# macropad_v1.net
KiCad netlist of a schematic drawn in EAGLE
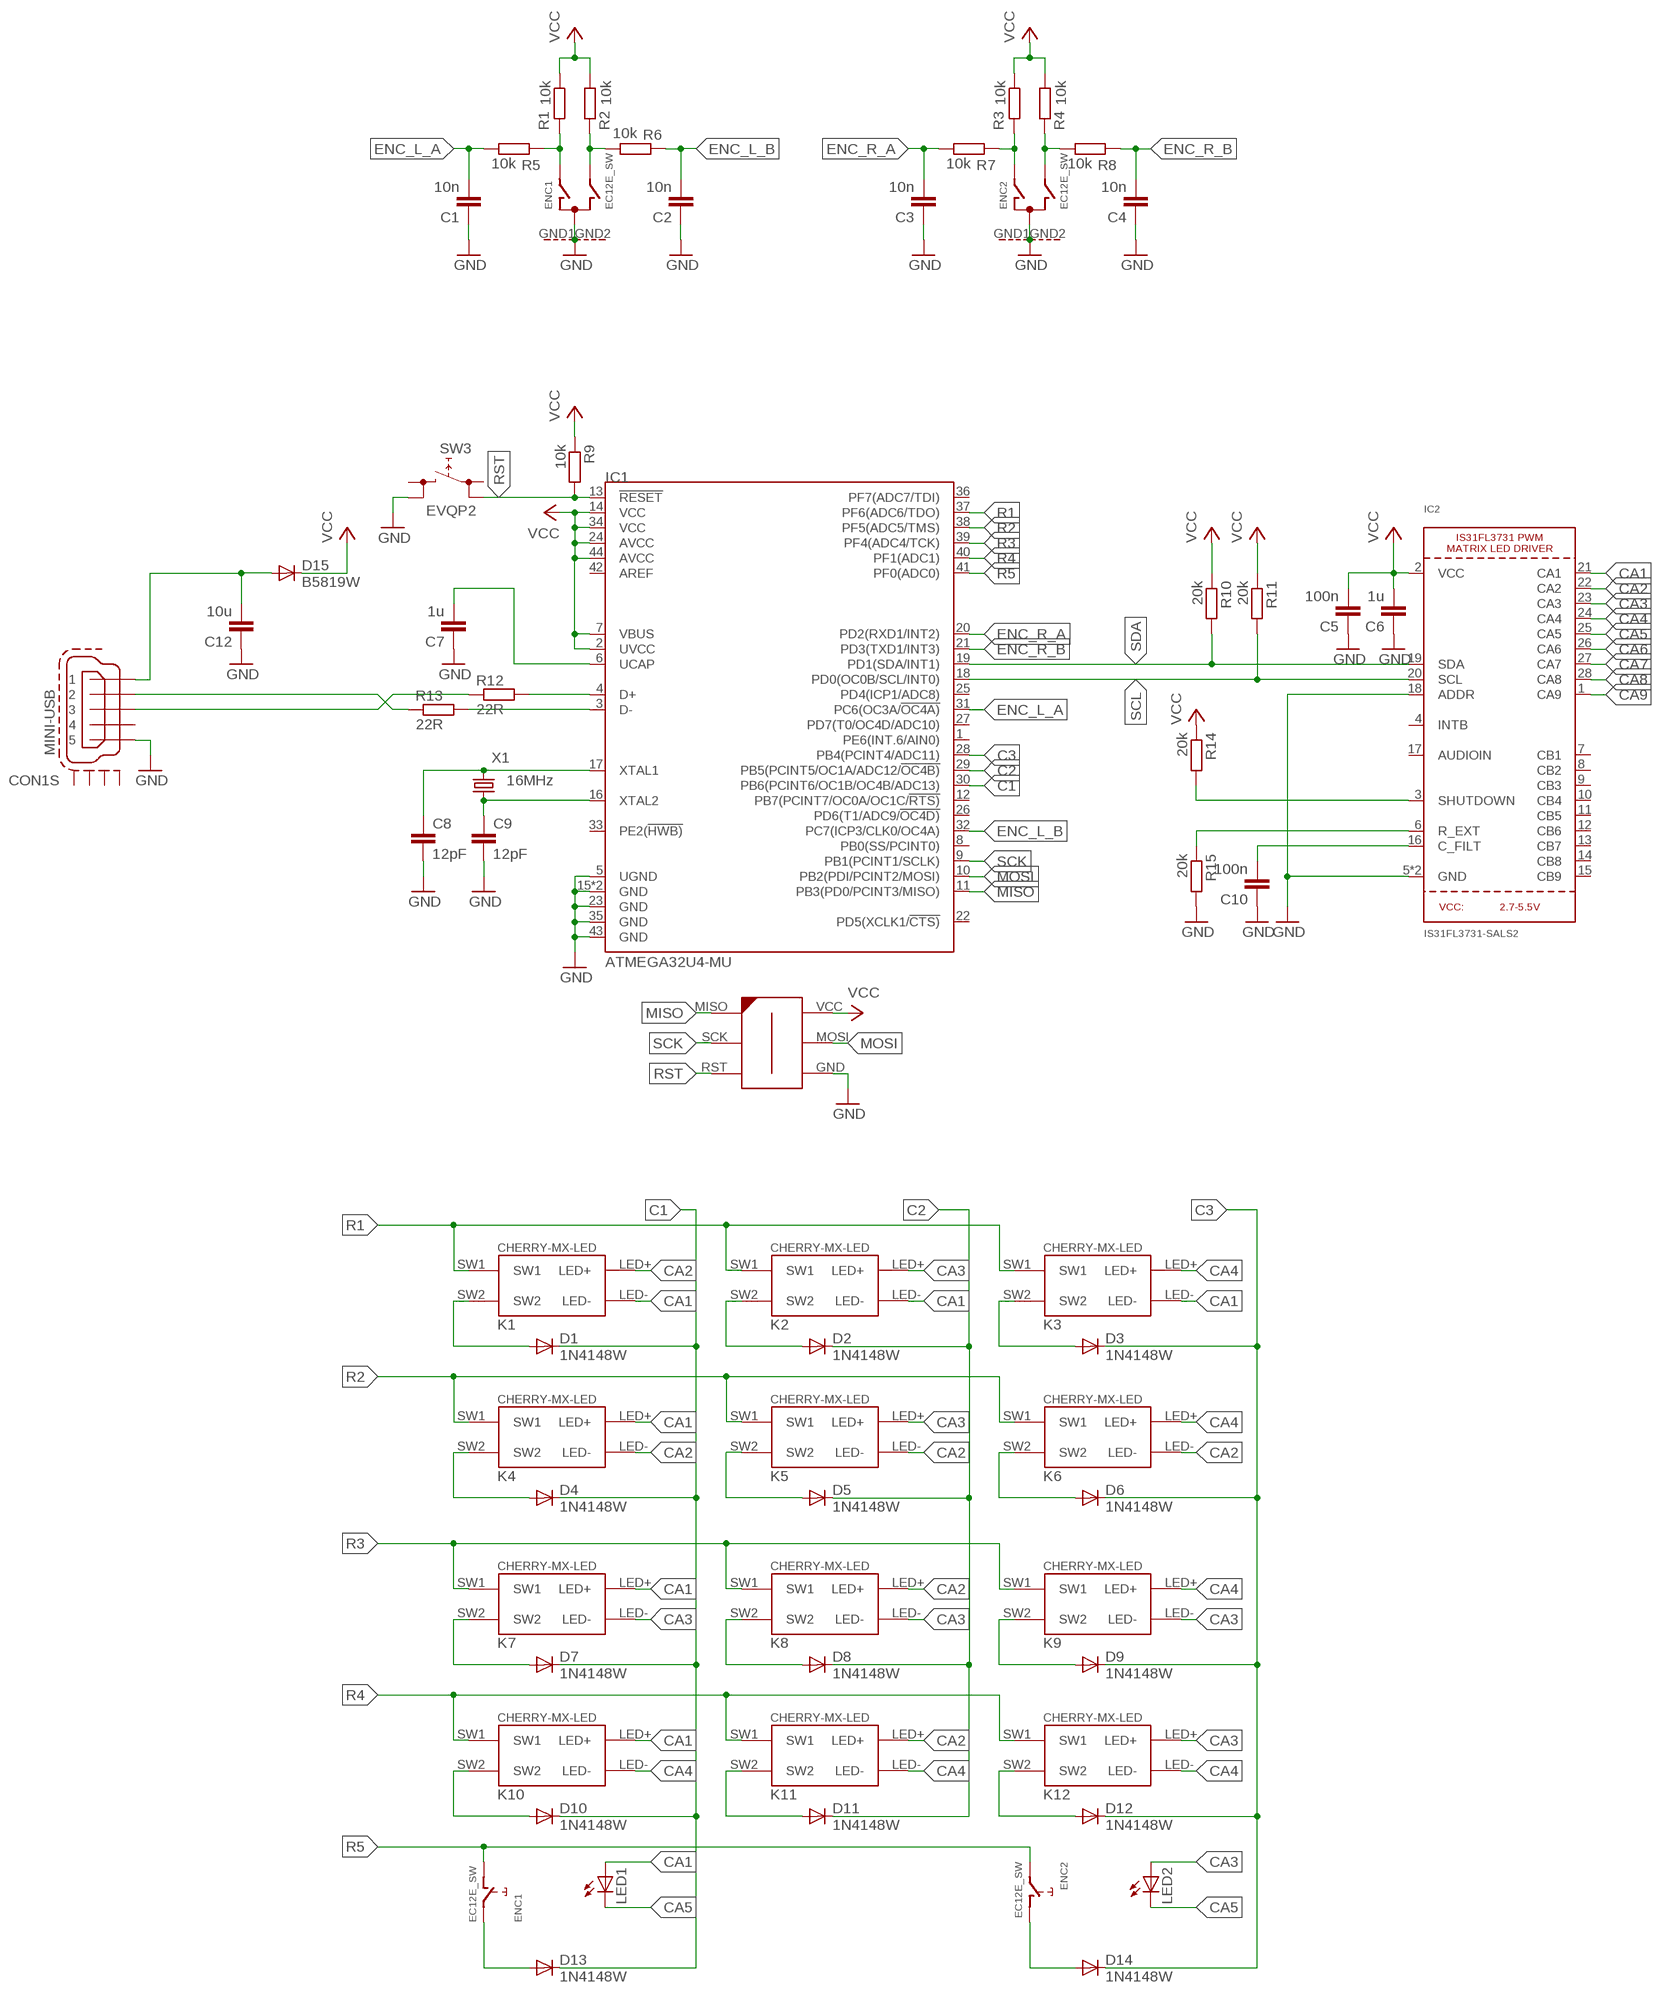
[diagram p0: schematic, sheet 1]

(export (version "E")
  (design (tool "Eeschema 10.0.6"))
  (components
    (comp (ref "C1")
      (value "10n")
      (footprint "eagle-import:C0603")
      (libsource (lib "eagle-import") (part "C-EUC0603"))
    )
    (comp (ref "C2")
      (value "10n")
      (footprint "eagle-import:C0603")
      (libsource (lib "eagle-import") (part "C-EUC0603"))
    )
    (comp (ref "C3")
      (value "10n")
      (footprint "eagle-import:C0603")
      (libsource (lib "eagle-import") (part "C-EUC0603"))
    )
    (comp (ref "C4")
      (value "10n")
      (footprint "eagle-import:C0603")
      (libsource (lib "eagle-import") (part "C-EUC0603"))
    )
    (comp (ref "C5")
      (value "100n")
      (footprint "eagle-import:C0603")
      (libsource (lib "eagle-import") (part "C-EUC0603"))
    )
    (comp (ref "C6")
      (value "1u")
      (footprint "eagle-import:C0603")
      (libsource (lib "eagle-import") (part "C-EUC0603"))
    )
    (comp (ref "C7")
      (value "1u")
      (footprint "eagle-import:C0603")
      (libsource (lib "eagle-import") (part "C-EUC0603"))
    )
    (comp (ref "C8")
      (value "12pF")
      (footprint "eagle-import:C0603")
      (libsource (lib "eagle-import") (part "C-EUC0603"))
    )
    (comp (ref "C9")
      (value "12pF")
      (footprint "eagle-import:C0603")
      (libsource (lib "eagle-import") (part "C-EUC0603"))
    )
    (comp (ref "C10")
      (value "100n")
      (footprint "eagle-import:C0603")
      (libsource (lib "eagle-import") (part "C-EUC0603"))
    )
    (comp (ref "C12")
      (value "10u")
      (footprint "eagle-import:C0603")
      (libsource (lib "eagle-import") (part "C-EUC0603"))
    )
    (comp (ref "CON1")
      (value "MINI-USB")
      (footprint "eagle-import:32005-201")
      (libsource (lib "eagle-import") (part "MINI-USB-SCHIELD-32005-201"))
    )
    (comp (ref "D1")
      (value "1N4148W")
      (footprint "eagle-import:SOD123")
      (libsource (lib "eagle-import") (part "DIODE-SOD123"))
    )
    (comp (ref "D2")
      (value "1N4148W")
      (footprint "eagle-import:SOD123")
      (libsource (lib "eagle-import") (part "DIODE-SOD123"))
    )
    (comp (ref "D3")
      (value "1N4148W")
      (footprint "eagle-import:SOD123")
      (libsource (lib "eagle-import") (part "DIODE-SOD123"))
    )
    (comp (ref "D4")
      (value "1N4148W")
      (footprint "eagle-import:SOD123")
      (libsource (lib "eagle-import") (part "DIODE-SOD123"))
    )
    (comp (ref "D5")
      (value "1N4148W")
      (footprint "eagle-import:SOD123")
      (libsource (lib "eagle-import") (part "DIODE-SOD123"))
    )
    (comp (ref "D6")
      (value "1N4148W")
      (footprint "eagle-import:SOD123")
      (libsource (lib "eagle-import") (part "DIODE-SOD123"))
    )
    (comp (ref "D7")
      (value "1N4148W")
      (footprint "eagle-import:SOD123")
      (libsource (lib "eagle-import") (part "DIODE-SOD123"))
    )
    (comp (ref "D8")
      (value "1N4148W")
      (footprint "eagle-import:SOD123")
      (libsource (lib "eagle-import") (part "DIODE-SOD123"))
    )
    (comp (ref "D9")
      (value "1N4148W")
      (footprint "eagle-import:SOD123")
      (libsource (lib "eagle-import") (part "DIODE-SOD123"))
    )
    (comp (ref "D10")
      (value "1N4148W")
      (footprint "eagle-import:SOD123")
      (libsource (lib "eagle-import") (part "DIODE-SOD123"))
    )
    (comp (ref "D11")
      (value "1N4148W")
      (footprint "eagle-import:SOD123")
      (libsource (lib "eagle-import") (part "DIODE-SOD123"))
    )
    (comp (ref "D12")
      (value "1N4148W")
      (footprint "eagle-import:SOD123")
      (libsource (lib "eagle-import") (part "DIODE-SOD123"))
    )
    (comp (ref "D13")
      (value "1N4148W")
      (footprint "eagle-import:SOD123")
      (libsource (lib "eagle-import") (part "DIODE-SOD123"))
    )
    (comp (ref "D14")
      (value "1N4148W")
      (footprint "eagle-import:SOD123")
      (libsource (lib "eagle-import") (part "DIODE-SOD123"))
    )
    (comp (ref "D15")
      (value "B5819W")
      (footprint "eagle-import:SOD123")
      (libsource (lib "eagle-import") (part "DIODE-SOD123"))
    )
    (comp (ref "ENC1")
      (value "EC12E_SW")
      (footprint "eagle-import:ALPS_EC12E_SW")
      (fields (field (name "MPN") "EC12E2424407"))
      (libsource (lib "eagle-import") (part "EC12E_SW"))
    )
    (comp (ref "ENC2")
      (value "EC12E_SW")
      (footprint "eagle-import:ALPS_EC12E_SW")
      (fields (field (name "MPN") "EC12E2424407"))
      (libsource (lib "eagle-import") (part "EC12E_SW"))
    )
    (comp (ref "IC1")
      (value "ATMEGA32U4-MU")
      (footprint "eagle-import:QFN44G-0.5-7X7MM")
      (fields (field (name "MF") "Microchip") (field (name "MP") "ATMEGA32U4-MUR"))
      (libsource (lib "eagle-import") (part "MCU-ATMEGA32U4-MUR(VQFN44)"))
    )
    (comp (ref "IC2")
      (value "IS31FL3731-SALS2")
      (footprint "eagle-import:QFN28_4MM_0.4MM")
      (libsource (lib "eagle-import") (part "IS31FL3731QFN"))
    )
    (comp (ref "K1")
      (value "CHERRY-MX-LED")
      (footprint "eagle-import:CHERRY-MX-LED")
      (libsource (lib "eagle-import") (part "CHERRY-MX-LED"))
    )
    (comp (ref "K2")
      (value "CHERRY-MX-LED")
      (footprint "eagle-import:CHERRY-MX-LED")
      (libsource (lib "eagle-import") (part "CHERRY-MX-LED"))
    )
    (comp (ref "K3")
      (value "CHERRY-MX-LED")
      (footprint "eagle-import:CHERRY-MX-LED")
      (libsource (lib "eagle-import") (part "CHERRY-MX-LED"))
    )
    (comp (ref "K4")
      (value "CHERRY-MX-LED")
      (footprint "eagle-import:CHERRY-MX-LED")
      (libsource (lib "eagle-import") (part "CHERRY-MX-LED"))
    )
    (comp (ref "K5")
      (value "CHERRY-MX-LED")
      (footprint "eagle-import:CHERRY-MX-LED")
      (libsource (lib "eagle-import") (part "CHERRY-MX-LED"))
    )
    (comp (ref "K6")
      (value "CHERRY-MX-LED")
      (footprint "eagle-import:CHERRY-MX-LED")
      (libsource (lib "eagle-import") (part "CHERRY-MX-LED"))
    )
    (comp (ref "K7")
      (value "CHERRY-MX-LED")
      (footprint "eagle-import:CHERRY-MX-LED")
      (libsource (lib "eagle-import") (part "CHERRY-MX-LED"))
    )
    (comp (ref "K8")
      (value "CHERRY-MX-LED")
      (footprint "eagle-import:CHERRY-MX-LED")
      (libsource (lib "eagle-import") (part "CHERRY-MX-LED"))
    )
    (comp (ref "K9")
      (value "CHERRY-MX-LED")
      (footprint "eagle-import:CHERRY-MX-LED")
      (libsource (lib "eagle-import") (part "CHERRY-MX-LED"))
    )
    (comp (ref "K10")
      (value "CHERRY-MX-LED")
      (footprint "eagle-import:CHERRY-MX-LED")
      (libsource (lib "eagle-import") (part "CHERRY-MX-LED"))
    )
    (comp (ref "K11")
      (value "CHERRY-MX-LED")
      (footprint "eagle-import:CHERRY-MX-LED")
      (libsource (lib "eagle-import") (part "CHERRY-MX-LED"))
    )
    (comp (ref "K12")
      (value "CHERRY-MX-LED")
      (footprint "eagle-import:CHERRY-MX-LED")
      (libsource (lib "eagle-import") (part "CHERRY-MX-LED"))
    )
    (comp (ref "LED1")
      (value "LED3MM")
      (footprint "eagle-import:LED3MM")
      (libsource (lib "eagle-import") (part "LED3MM"))
    )
    (comp (ref "LED2")
      (value "LED3MM")
      (footprint "eagle-import:LED3MM")
      (libsource (lib "eagle-import") (part "LED3MM"))
    )
    (comp (ref "R1")
      (value "10k")
      (footprint "eagle-import:R0603")
      (libsource (lib "eagle-import") (part "R-EU_R0603"))
    )
    (comp (ref "R2")
      (value "10k")
      (footprint "eagle-import:R0603")
      (libsource (lib "eagle-import") (part "R-EU_R0603"))
    )
    (comp (ref "R3")
      (value "10k")
      (footprint "eagle-import:R0603")
      (libsource (lib "eagle-import") (part "R-EU_R0603"))
    )
    (comp (ref "R4")
      (value "10k")
      (footprint "eagle-import:R0603")
      (libsource (lib "eagle-import") (part "R-EU_R0603"))
    )
    (comp (ref "R5")
      (value "10k")
      (footprint "eagle-import:R0603")
      (libsource (lib "eagle-import") (part "R-EU_R0603"))
    )
    (comp (ref "R6")
      (value "10k")
      (footprint "eagle-import:R0603")
      (libsource (lib "eagle-import") (part "R-EU_R0603"))
    )
    (comp (ref "R7")
      (value "10k")
      (footprint "eagle-import:R0603")
      (libsource (lib "eagle-import") (part "R-EU_R0603"))
    )
    (comp (ref "R8")
      (value "10k")
      (footprint "eagle-import:R0603")
      (libsource (lib "eagle-import") (part "R-EU_R0603"))
    )
    (comp (ref "R9")
      (value "10k")
      (footprint "eagle-import:R0603")
      (libsource (lib "eagle-import") (part "R-EU_R0603"))
    )
    (comp (ref "R10")
      (value "20k")
      (footprint "eagle-import:R0603")
      (libsource (lib "eagle-import") (part "R-EU_R0603"))
    )
    (comp (ref "R11")
      (value "20k")
      (footprint "eagle-import:R0603")
      (libsource (lib "eagle-import") (part "R-EU_R0603"))
    )
    (comp (ref "R12")
      (value "22R")
      (footprint "eagle-import:R0603")
      (libsource (lib "eagle-import") (part "R-EU_R0603"))
    )
    (comp (ref "R13")
      (value "22R")
      (footprint "eagle-import:R0603")
      (libsource (lib "eagle-import") (part "R-EU_R0603"))
    )
    (comp (ref "R14")
      (value "20k")
      (footprint "eagle-import:R0603")
      (libsource (lib "eagle-import") (part "R-EU_R0603"))
    )
    (comp (ref "R15")
      (value "20k")
      (footprint "eagle-import:R0603")
      (libsource (lib "eagle-import") (part "R-EU_R0603"))
    )
    (comp (ref "SW3")
      (value "EVQP2")
      (footprint "eagle-import:EVQP2")
      (libsource (lib "eagle-import") (part "EVQP2"))
    )
    (comp (ref "U$1")
      (value "AVR-ISP-6-EDGE")
      (footprint "eagle-import:6PAD_ISP")
      (libsource (lib "eagle-import") (part "AVR-ISP-6-EDGE"))
    )
    (comp (ref "X1")
      (value "16MHz")
      (footprint "eagle-import:3.2X2.5_KX-7")
      (libsource (lib "eagle-import") (part "KX-7"))
    )
  )
  (nets
    (net (code "1") (name "C1") (class "Default")
      (node (ref "D1") (pin "C") (pinfunction "C_C") (pintype "passive"))
      (node (ref "D10") (pin "C") (pinfunction "C_C") (pintype "passive"))
      (node (ref "D13") (pin "C") (pinfunction "C_C") (pintype "passive"))
      (node (ref "D4") (pin "C") (pinfunction "C_C") (pintype "passive"))
      (node (ref "D7") (pin "C") (pinfunction "C_C") (pintype "passive"))
      (node (ref "IC1") (pin "30") (pinfunction "PB6(PCINT6/OC1B/OC4B/ADC13)_30") (pintype "bidirectional"))
    )
    (net (code "2") (name "C2") (class "Default")
      (node (ref "D11") (pin "C") (pinfunction "C_C") (pintype "passive"))
      (node (ref "D2") (pin "C") (pinfunction "C_C") (pintype "passive"))
      (node (ref "D5") (pin "C") (pinfunction "C_C") (pintype "passive"))
      (node (ref "D8") (pin "C") (pinfunction "C_C") (pintype "passive"))
      (node (ref "IC1") (pin "29") (pinfunction "PB5(PCINT5/OC1A/ADC12/~{OC4B})_29") (pintype "bidirectional"))
    )
    (net (code "3") (name "C3") (class "Default")
      (node (ref "D12") (pin "C") (pinfunction "C_C") (pintype "passive"))
      (node (ref "D14") (pin "C") (pinfunction "C_C") (pintype "passive"))
      (node (ref "D3") (pin "C") (pinfunction "C_C") (pintype "passive"))
      (node (ref "D6") (pin "C") (pinfunction "C_C") (pintype "passive"))
      (node (ref "D9") (pin "C") (pinfunction "C_C") (pintype "passive"))
      (node (ref "IC1") (pin "28") (pinfunction "PB4(PCINT4/ADC11)_28") (pintype "bidirectional"))
    )
    (net (code "4") (name "CA1") (class "Default")
      (node (ref "IC2") (pin "21") (pinfunction "CA1_21") (pintype "bidirectional"))
      (node (ref "K1") (pin "LED-") (pinfunction "LED-_LED-") (pintype "bidirectional"))
      (node (ref "K10") (pin "LED+") (pinfunction "LED+_LED+") (pintype "bidirectional"))
      (node (ref "K2") (pin "LED-") (pinfunction "LED-_LED-") (pintype "bidirectional"))
      (node (ref "K3") (pin "LED-") (pinfunction "LED-_LED-") (pintype "bidirectional"))
      (node (ref "K4") (pin "LED+") (pinfunction "LED+_LED+") (pintype "bidirectional"))
      (node (ref "K7") (pin "LED+") (pinfunction "LED+_LED+") (pintype "bidirectional"))
      (node (ref "LED1") (pin "A") (pinfunction "A_A") (pintype "passive"))
    )
    (net (code "5") (name "CA2") (class "Default")
      (node (ref "IC2") (pin "22") (pinfunction "CA2_22") (pintype "bidirectional"))
      (node (ref "K1") (pin "LED+") (pinfunction "LED+_LED+") (pintype "bidirectional"))
      (node (ref "K11") (pin "LED+") (pinfunction "LED+_LED+") (pintype "bidirectional"))
      (node (ref "K4") (pin "LED-") (pinfunction "LED-_LED-") (pintype "bidirectional"))
      (node (ref "K5") (pin "LED-") (pinfunction "LED-_LED-") (pintype "bidirectional"))
      (node (ref "K6") (pin "LED-") (pinfunction "LED-_LED-") (pintype "bidirectional"))
      (node (ref "K8") (pin "LED+") (pinfunction "LED+_LED+") (pintype "bidirectional"))
    )
    (net (code "6") (name "CA3") (class "Default")
      (node (ref "IC2") (pin "23") (pinfunction "CA3_23") (pintype "bidirectional"))
      (node (ref "K12") (pin "LED+") (pinfunction "LED+_LED+") (pintype "bidirectional"))
      (node (ref "K2") (pin "LED+") (pinfunction "LED+_LED+") (pintype "bidirectional"))
      (node (ref "K5") (pin "LED+") (pinfunction "LED+_LED+") (pintype "bidirectional"))
      (node (ref "K7") (pin "LED-") (pinfunction "LED-_LED-") (pintype "bidirectional"))
      (node (ref "K8") (pin "LED-") (pinfunction "LED-_LED-") (pintype "bidirectional"))
      (node (ref "K9") (pin "LED-") (pinfunction "LED-_LED-") (pintype "bidirectional"))
      (node (ref "LED2") (pin "A") (pinfunction "A_A") (pintype "passive"))
    )
    (net (code "7") (name "CA4") (class "Default")
      (node (ref "IC2") (pin "24") (pinfunction "CA4_24") (pintype "bidirectional"))
      (node (ref "K10") (pin "LED-") (pinfunction "LED-_LED-") (pintype "bidirectional"))
      (node (ref "K11") (pin "LED-") (pinfunction "LED-_LED-") (pintype "bidirectional"))
      (node (ref "K12") (pin "LED-") (pinfunction "LED-_LED-") (pintype "bidirectional"))
      (node (ref "K3") (pin "LED+") (pinfunction "LED+_LED+") (pintype "bidirectional"))
      (node (ref "K6") (pin "LED+") (pinfunction "LED+_LED+") (pintype "bidirectional"))
      (node (ref "K9") (pin "LED+") (pinfunction "LED+_LED+") (pintype "bidirectional"))
    )
    (net (code "8") (name "CA5") (class "Default")
      (node (ref "IC2") (pin "25") (pinfunction "CA5_25") (pintype "bidirectional"))
      (node (ref "LED1") (pin "K") (pinfunction "C_K") (pintype "passive"))
      (node (ref "LED2") (pin "K") (pinfunction "C_K") (pintype "passive"))
    )
    (net (code "9") (name "CA6") (class "Default")
      (node (ref "IC2") (pin "26") (pinfunction "CA6_26") (pintype "bidirectional"))
    )
    (net (code "10") (name "CA7") (class "Default")
      (node (ref "IC2") (pin "27") (pinfunction "CA7_27") (pintype "bidirectional"))
    )
    (net (code "11") (name "CA8") (class "Default")
      (node (ref "IC2") (pin "28") (pinfunction "CA8_28") (pintype "bidirectional"))
    )
    (net (code "12") (name "CA9") (class "Default")
      (node (ref "IC2") (pin "1") (pinfunction "CA9_1") (pintype "bidirectional"))
    )
    (net (code "13") (name "ENC_L_A") (class "Default")
      (node (ref "C1") (pin "2") (pinfunction "2_2") (pintype "passive"))
      (node (ref "IC1") (pin "31") (pinfunction "PC6(OC3A/~{OC4A})_31") (pintype "bidirectional"))
      (node (ref "R5") (pin "1") (pinfunction "1_1") (pintype "passive"))
    )
    (net (code "14") (name "ENC_L_B") (class "Default")
      (node (ref "C2") (pin "2") (pinfunction "2_2") (pintype "passive"))
      (node (ref "IC1") (pin "32") (pinfunction "PC7(ICP3/CLK0/OC4A)_32") (pintype "bidirectional"))
      (node (ref "R6") (pin "2") (pinfunction "2_2") (pintype "passive"))
    )
    (net (code "15") (name "ENC_R_A") (class "Default")
      (node (ref "C3") (pin "2") (pinfunction "2_2") (pintype "passive"))
      (node (ref "IC1") (pin "20") (pinfunction "PD2(RXD1/INT2)_20") (pintype "bidirectional"))
      (node (ref "R7") (pin "1") (pinfunction "1_1") (pintype "passive"))
    )
    (net (code "16") (name "ENC_R_B") (class "Default")
      (node (ref "C4") (pin "2") (pinfunction "2_2") (pintype "passive"))
      (node (ref "IC1") (pin "21") (pinfunction "PD3(TXD1/INT3)_21") (pintype "bidirectional"))
      (node (ref "R8") (pin "2") (pinfunction "2_2") (pintype "passive"))
    )
    (net (code "17") (name "GND") (class "Default")
      (node (ref "C1") (pin "1") (pinfunction "1_1") (pintype "passive"))
      (node (ref "C10") (pin "1") (pinfunction "1_1") (pintype "passive"))
      (node (ref "C12") (pin "1") (pinfunction "1_1") (pintype "passive"))
      (node (ref "C2") (pin "1") (pinfunction "1_1") (pintype "passive"))
      (node (ref "C3") (pin "1") (pinfunction "1_1") (pintype "passive"))
      (node (ref "C4") (pin "1") (pinfunction "1_1") (pintype "passive"))
      (node (ref "C5") (pin "1") (pinfunction "1_1") (pintype "passive"))
      (node (ref "C6") (pin "1") (pinfunction "1_1") (pintype "passive"))
      (node (ref "C7") (pin "1") (pinfunction "1_1") (pintype "passive"))
      (node (ref "C8") (pin "2") (pinfunction "2_2") (pintype "passive"))
      (node (ref "C9") (pin "2") (pinfunction "2_2") (pintype "passive"))
      (node (ref "CON1") (pin "5") (pinfunction "5_5") (pintype "passive"))
      (node (ref "ENC1") (pin "C") (pinfunction "C_C") (pintype "passive"))
      (node (ref "ENC1") (pin "GND1") (pinfunction "G_GND1") (pintype "passive"))
      (node (ref "ENC1") (pin "GND2") (pinfunction "G_GND2") (pintype "passive"))
      (node (ref "ENC2") (pin "C") (pinfunction "C_C") (pintype "passive"))
      (node (ref "ENC2") (pin "GND1") (pinfunction "G_GND1") (pintype "passive"))
      (node (ref "ENC2") (pin "GND2") (pinfunction "G_GND2") (pintype "passive"))
      (node (ref "IC1") (pin "15") (pinfunction "GND_15") (pintype "bidirectional"))
      (node (ref "IC1") (pin "23") (pinfunction "GND_23") (pintype "bidirectional"))
      (node (ref "IC1") (pin "35") (pinfunction "GND_35") (pintype "bidirectional"))
      (node (ref "IC1") (pin "43") (pinfunction "GND_43") (pintype "bidirectional"))
      (node (ref "IC1") (pin "5") (pinfunction "UGND_5") (pintype "bidirectional"))
      (node (ref "IC1") (pin "TAB") (pinfunction "GND_TAB") (pintype "bidirectional"))
      (node (ref "IC2") (pin "18") (pinfunction "ADDR_18") (pintype "bidirectional"))
      (node (ref "IC2") (pin "5") (pinfunction "GND_5") (pintype "power_in"))
      (node (ref "IC2") (pin "THERMAL") (pinfunction "GND_THERMAL") (pintype "power_in"))
      (node (ref "R15") (pin "2") (pinfunction "2_2") (pintype "passive"))
      (node (ref "SW3") (pin "2") (pinfunction "1_2") (pintype "passive"))
      (node (ref "U$1") (pin "GND") (pinfunction "P$4_GND") (pintype "bidirectional"))
    )
    (net (code "18") (name "MISO") (class "Default")
      (node (ref "IC1") (pin "11") (pinfunction "PB3(PD0/PCINT3/MISO)_11") (pintype "bidirectional"))
      (node (ref "U$1") (pin "MISO") (pinfunction "P$1_MISO") (pintype "bidirectional"))
    )
    (net (code "19") (name "MOSI") (class "Default")
      (node (ref "IC1") (pin "10") (pinfunction "PB2(PDI/PCINT2/MOSI)_10") (pintype "bidirectional"))
      (node (ref "U$1") (pin "MOSI") (pinfunction "P$5_MOSI") (pintype "bidirectional"))
    )
    (net (code "20") (name "Net-(C12-Pad2)") (class "Default")
      (node (ref "C12") (pin "2") (pinfunction "2_2") (pintype "passive"))
      (node (ref "CON1") (pin "1") (pinfunction "1_1") (pintype "passive"))
      (node (ref "D15") (pin "A") (pinfunction "A_A") (pintype "passive"))
    )
    (net (code "21") (name "Net-(CON1-Pad2)") (class "Default")
      (node (ref "CON1") (pin "2") (pinfunction "2_2") (pintype "passive"))
      (node (ref "R13") (pin "1") (pinfunction "1_1") (pintype "passive"))
    )
    (net (code "22") (name "Net-(CON1-Pad3)") (class "Default")
      (node (ref "CON1") (pin "3") (pinfunction "3_3") (pintype "passive"))
      (node (ref "R12") (pin "1") (pinfunction "1_1") (pintype "passive"))
    )
    (net (code "23") (name "Net-(D1-PadA)") (class "Default")
      (node (ref "D1") (pin "A") (pinfunction "A_A") (pintype "passive"))
      (node (ref "K1") (pin "SW2") (pinfunction "SW2_SW2") (pintype "bidirectional"))
    )
    (net (code "24") (name "Net-(D2-PadA)") (class "Default")
      (node (ref "D2") (pin "A") (pinfunction "A_A") (pintype "passive"))
      (node (ref "K2") (pin "SW2") (pinfunction "SW2_SW2") (pintype "bidirectional"))
    )
    (net (code "25") (name "Net-(D3-PadA)") (class "Default")
      (node (ref "D3") (pin "A") (pinfunction "A_A") (pintype "passive"))
      (node (ref "K3") (pin "SW2") (pinfunction "SW2_SW2") (pintype "bidirectional"))
    )
    (net (code "26") (name "Net-(D4-PadA)") (class "Default")
      (node (ref "D4") (pin "A") (pinfunction "A_A") (pintype "passive"))
      (node (ref "K4") (pin "SW2") (pinfunction "SW2_SW2") (pintype "bidirectional"))
    )
    (net (code "27") (name "Net-(D5-PadA)") (class "Default")
      (node (ref "D5") (pin "A") (pinfunction "A_A") (pintype "passive"))
      (node (ref "K5") (pin "SW2") (pinfunction "SW2_SW2") (pintype "bidirectional"))
    )
    (net (code "28") (name "Net-(D6-PadA)") (class "Default")
      (node (ref "D6") (pin "A") (pinfunction "A_A") (pintype "passive"))
      (node (ref "K6") (pin "SW2") (pinfunction "SW2_SW2") (pintype "bidirectional"))
    )
    (net (code "29") (name "Net-(D7-PadA)") (class "Default")
      (node (ref "D7") (pin "A") (pinfunction "A_A") (pintype "passive"))
      (node (ref "K7") (pin "SW2") (pinfunction "SW2_SW2") (pintype "bidirectional"))
    )
    (net (code "30") (name "Net-(D8-PadA)") (class "Default")
      (node (ref "D8") (pin "A") (pinfunction "A_A") (pintype "passive"))
      (node (ref "K8") (pin "SW2") (pinfunction "SW2_SW2") (pintype "bidirectional"))
    )
    (net (code "31") (name "Net-(D9-PadA)") (class "Default")
      (node (ref "D9") (pin "A") (pinfunction "A_A") (pintype "passive"))
      (node (ref "K9") (pin "SW2") (pinfunction "SW2_SW2") (pintype "bidirectional"))
    )
    (net (code "32") (name "Net-(D10-PadA)") (class "Default")
      (node (ref "D10") (pin "A") (pinfunction "A_A") (pintype "passive"))
      (node (ref "K10") (pin "SW2") (pinfunction "SW2_SW2") (pintype "bidirectional"))
    )
    (net (code "33") (name "Net-(D11-PadA)") (class "Default")
      (node (ref "D11") (pin "A") (pinfunction "A_A") (pintype "passive"))
      (node (ref "K11") (pin "SW2") (pinfunction "SW2_SW2") (pintype "bidirectional"))
    )
    (net (code "34") (name "Net-(D12-PadA)") (class "Default")
      (node (ref "D12") (pin "A") (pinfunction "A_A") (pintype "passive"))
      (node (ref "K12") (pin "SW2") (pinfunction "SW2_SW2") (pintype "bidirectional"))
    )
    (net (code "35") (name "Net-(ENC1-PadA)") (class "Default")
      (node (ref "ENC1") (pin "A") (pinfunction "A_A") (pintype "passive"))
      (node (ref "R1") (pin "2") (pinfunction "2_2") (pintype "passive"))
      (node (ref "R5") (pin "2") (pinfunction "2_2") (pintype "passive"))
    )
    (net (code "36") (name "Net-(ENC1-PadB)") (class "Default")
      (node (ref "ENC1") (pin "B") (pinfunction "B_B") (pintype "passive"))
      (node (ref "R2") (pin "2") (pinfunction "2_2") (pintype "passive"))
      (node (ref "R6") (pin "1") (pinfunction "1_1") (pintype "passive"))
    )
    (net (code "37") (name "Net-(ENC1B-2)") (class "Default")
      (node (ref "D13") (pin "A") (pinfunction "A_A") (pintype "passive"))
      (node (ref "ENC1") (pin "E") (pinfunction "2_E") (pintype "passive"))
    )
    (net (code "38") (name "Net-(ENC2-PadA)") (class "Default")
      (node (ref "ENC2") (pin "A") (pinfunction "A_A") (pintype "passive"))
      (node (ref "R3") (pin "2") (pinfunction "2_2") (pintype "passive"))
      (node (ref "R7") (pin "2") (pinfunction "2_2") (pintype "passive"))
    )
    (net (code "39") (name "Net-(ENC2-PadB)") (class "Default")
      (node (ref "ENC2") (pin "B") (pinfunction "B_B") (pintype "passive"))
      (node (ref "R4") (pin "2") (pinfunction "2_2") (pintype "passive"))
      (node (ref "R8") (pin "1") (pinfunction "1_1") (pintype "passive"))
    )
    (net (code "40") (name "Net-(ENC2B-1)") (class "Default")
      (node (ref "D14") (pin "A") (pinfunction "A_A") (pintype "passive"))
      (node (ref "ENC2") (pin "D") (pinfunction "1_D") (pintype "passive"))
    )
    (net (code "41") (name "Net-(IC1-D+)") (class "Default")
      (node (ref "IC1") (pin "4") (pinfunction "D+_4") (pintype "bidirectional"))
      (node (ref "R12") (pin "2") (pinfunction "2_2") (pintype "passive"))
    )
    (net (code "42") (name "Net-(IC1-D-)") (class "Default")
      (node (ref "IC1") (pin "3") (pinfunction "D-_3") (pintype "bidirectional"))
      (node (ref "R13") (pin "2") (pinfunction "2_2") (pintype "passive"))
    )
    (net (code "43") (name "Net-(IC1-UCAP)") (class "Default")
      (node (ref "C7") (pin "2") (pinfunction "2_2") (pintype "passive"))
      (node (ref "IC1") (pin "6") (pinfunction "UCAP_6") (pintype "bidirectional"))
    )
    (net (code "44") (name "Net-(IC1-XTAL1)") (class "Default")
      (node (ref "C8") (pin "1") (pinfunction "1_1") (pintype "passive"))
      (node (ref "IC1") (pin "17") (pinfunction "XTAL1_17") (pintype "bidirectional"))
      (node (ref "X1") (pin "3") (pinfunction "2_3") (pintype "passive"))
    )
    (net (code "45") (name "Net-(IC1-XTAL2)") (class "Default")
      (node (ref "C9") (pin "1") (pinfunction "1_1") (pintype "passive"))
      (node (ref "IC1") (pin "16") (pinfunction "XTAL2_16") (pintype "bidirectional"))
      (node (ref "X1") (pin "1") (pinfunction "1_1") (pintype "passive"))
    )
    (net (code "46") (name "Net-(IC2-C_FILT)") (class "Default")
      (node (ref "C10") (pin "2") (pinfunction "2_2") (pintype "passive"))
      (node (ref "IC2") (pin "16") (pinfunction "C_FILT_16") (pintype "bidirectional"))
    )
    (net (code "47") (name "Net-(IC2-R_EXT)") (class "Default")
      (node (ref "IC2") (pin "6") (pinfunction "R_EXT_6") (pintype "bidirectional"))
      (node (ref "R15") (pin "1") (pinfunction "1_1") (pintype "passive"))
    )
    (net (code "48") (name "Net-(IC2-SHUTDOWN)") (class "Default")
      (node (ref "IC2") (pin "3") (pinfunction "SHUTDOWN_3") (pintype "input"))
      (node (ref "R14") (pin "2") (pinfunction "2_2") (pintype "passive"))
    )
    (net (code "49") (name "R1") (class "Default")
      (node (ref "IC1") (pin "37") (pinfunction "PF6(ADC6/TDO)_37") (pintype "bidirectional"))
      (node (ref "K1") (pin "SW1") (pinfunction "SW1_SW1") (pintype "bidirectional"))
      (node (ref "K2") (pin "SW1") (pinfunction "SW1_SW1") (pintype "bidirectional"))
      (node (ref "K3") (pin "SW1") (pinfunction "SW1_SW1") (pintype "bidirectional"))
    )
    (net (code "50") (name "R2") (class "Default")
      (node (ref "IC1") (pin "38") (pinfunction "PF5(ADC5/TMS)_38") (pintype "bidirectional"))
      (node (ref "K4") (pin "SW1") (pinfunction "SW1_SW1") (pintype "bidirectional"))
      (node (ref "K5") (pin "SW1") (pinfunction "SW1_SW1") (pintype "bidirectional"))
      (node (ref "K6") (pin "SW1") (pinfunction "SW1_SW1") (pintype "bidirectional"))
    )
    (net (code "51") (name "R3") (class "Default")
      (node (ref "IC1") (pin "39") (pinfunction "PF4(ADC4/TCK)_39") (pintype "bidirectional"))
      (node (ref "K7") (pin "SW1") (pinfunction "SW1_SW1") (pintype "bidirectional"))
      (node (ref "K8") (pin "SW1") (pinfunction "SW1_SW1") (pintype "bidirectional"))
      (node (ref "K9") (pin "SW1") (pinfunction "SW1_SW1") (pintype "bidirectional"))
    )
    (net (code "52") (name "R4") (class "Default")
      (node (ref "IC1") (pin "40") (pinfunction "PF1(ADC1)_40") (pintype "bidirectional"))
      (node (ref "K10") (pin "SW1") (pinfunction "SW1_SW1") (pintype "bidirectional"))
      (node (ref "K11") (pin "SW1") (pinfunction "SW1_SW1") (pintype "bidirectional"))
      (node (ref "K12") (pin "SW1") (pinfunction "SW1_SW1") (pintype "bidirectional"))
    )
    (net (code "53") (name "R5") (class "Default")
      (node (ref "ENC1") (pin "D") (pinfunction "1_D") (pintype "passive"))
      (node (ref "ENC2") (pin "E") (pinfunction "2_E") (pintype "passive"))
      (node (ref "IC1") (pin "41") (pinfunction "PF0(ADC0)_41") (pintype "bidirectional"))
    )
    (net (code "54") (name "RST") (class "Default")
      (node (ref "IC1") (pin "13") (pinfunction "~{RESET}_13") (pintype "bidirectional"))
      (node (ref "R9") (pin "2") (pinfunction "2_2") (pintype "passive"))
      (node (ref "SW3") (pin "3") (pinfunction "0_3") (pintype "passive"))
      (node (ref "U$1") (pin "RST") (pinfunction "P$3_RST") (pintype "bidirectional"))
    )
    (net (code "55") (name "SCK") (class "Default")
      (node (ref "IC1") (pin "9") (pinfunction "PB1(PCINT1/SCLK)_9") (pintype "bidirectional"))
      (node (ref "U$1") (pin "SCK") (pinfunction "P$2_SCK") (pintype "bidirectional"))
    )
    (net (code "56") (name "SCL") (class "Default")
      (node (ref "IC1") (pin "18") (pinfunction "PD0(OC0B/SCL/INT0)_18") (pintype "bidirectional"))
      (node (ref "IC2") (pin "20") (pinfunction "SCL_20") (pintype "bidirectional"))
      (node (ref "R11") (pin "2") (pinfunction "2_2") (pintype "passive"))
    )
    (net (code "57") (name "SDA") (class "Default")
      (node (ref "IC1") (pin "19") (pinfunction "PD1(SDA/INT1)_19") (pintype "bidirectional"))
      (node (ref "IC2") (pin "19") (pinfunction "SDA_19") (pintype "bidirectional"))
      (node (ref "R10") (pin "2") (pinfunction "2_2") (pintype "passive"))
    )
    (net (code "58") (name "VCC") (class "Default")
      (node (ref "C5") (pin "2") (pinfunction "2_2") (pintype "passive"))
      (node (ref "C6") (pin "2") (pinfunction "2_2") (pintype "passive"))
      (node (ref "D15") (pin "C") (pinfunction "C_C") (pintype "passive"))
      (node (ref "IC1") (pin "14") (pinfunction "VCC_14") (pintype "bidirectional"))
      (node (ref "IC1") (pin "2") (pinfunction "UVCC_2") (pintype "bidirectional"))
      (node (ref "IC1") (pin "24") (pinfunction "AVCC_24") (pintype "bidirectional"))
      (node (ref "IC1") (pin "34") (pinfunction "VCC_34") (pintype "bidirectional"))
      (node (ref "IC1") (pin "44") (pinfunction "AVCC_44") (pintype "bidirectional"))
      (node (ref "IC1") (pin "7") (pinfunction "VBUS_7") (pintype "bidirectional"))
      (node (ref "IC2") (pin "2") (pinfunction "VCC_2") (pintype "power_in"))
      (node (ref "R1") (pin "1") (pinfunction "1_1") (pintype "passive"))
      (node (ref "R10") (pin "1") (pinfunction "1_1") (pintype "passive"))
      (node (ref "R11") (pin "1") (pinfunction "1_1") (pintype "passive"))
      (node (ref "R14") (pin "1") (pinfunction "1_1") (pintype "passive"))
      (node (ref "R2") (pin "1") (pinfunction "1_1") (pintype "passive"))
      (node (ref "R3") (pin "1") (pinfunction "1_1") (pintype "passive"))
      (node (ref "R4") (pin "1") (pinfunction "1_1") (pintype "passive"))
      (node (ref "R9") (pin "1") (pinfunction "1_1") (pintype "passive"))
      (node (ref "U$1") (pin "VCC") (pinfunction "P$6_VCC") (pintype "bidirectional"))
    )
    (net (code "59") (name "unconnected-(CON1-Pad4)") (class "Default")
      (node (ref "CON1") (pin "4") (pinfunction "4_4") (pintype "passive"))
    )
    (net (code "60") (name "unconnected-(CON1B-S1-PadM1)") (class "Default")
      (node (ref "CON1") (pin "M1") (pinfunction "S1_M1") (pintype "passive"))
    )
    (net (code "61") (name "unconnected-(CON1B-S2-PadM2)") (class "Default")
      (node (ref "CON1") (pin "M2") (pinfunction "S2_M2") (pintype "passive"))
    )
    (net (code "62") (name "unconnected-(CON1B-S3-PadM3)") (class "Default")
      (node (ref "CON1") (pin "M3") (pinfunction "S3_M3") (pintype "passive"))
    )
    (net (code "63") (name "unconnected-(CON1B-S4-PadM4)") (class "Default")
      (node (ref "CON1") (pin "M4") (pinfunction "S4_M4") (pintype "passive"))
    )
    (net (code "64") (name "unconnected-(IC1-AREF-Pad42)") (class "Default")
      (node (ref "IC1") (pin "42") (pinfunction "AREF_42") (pintype "bidirectional"))
    )
    (net (code "65") (name "unconnected-(IC1-PB0(SS{slash}PCINT0)-Pad8)") (class "Default")
      (node (ref "IC1") (pin "8") (pinfunction "PB0(SS/PCINT0)_8") (pintype "bidirectional"))
    )
    (net (code "66") (name "unconnected-(IC1-PB7(PCINT7{slash}OC0A{slash}OC1C{slash}~{RTS})-Pad12)") (class "Default")
      (node (ref "IC1") (pin "12") (pinfunction "PB7(PCINT7/OC0A/OC1C/~{RTS})_12") (pintype "bidirectional"))
    )
    (net (code "67") (name "unconnected-(IC1-PD4(ICP1{slash}ADC8)-Pad25)") (class "Default")
      (node (ref "IC1") (pin "25") (pinfunction "PD4(ICP1/ADC8)_25") (pintype "bidirectional"))
    )
    (net (code "68") (name "unconnected-(IC1-PD5(XCLK1{slash}~{CTS})-Pad22)") (class "Default")
      (node (ref "IC1") (pin "22") (pinfunction "PD5(XCLK1/~{CTS})_22") (pintype "bidirectional"))
    )
    (net (code "69") (name "unconnected-(IC1-PD6(T1{slash}ADC9{slash}~{OC4D})-Pad26)") (class "Default")
      (node (ref "IC1") (pin "26") (pinfunction "PD6(T1/ADC9/~{OC4D})_26") (pintype "bidirectional"))
    )
    (net (code "70") (name "unconnected-(IC1-PD7(T0{slash}OC4D{slash}ADC10)-Pad27)") (class "Default")
      (node (ref "IC1") (pin "27") (pinfunction "PD7(T0/OC4D/ADC10)_27") (pintype "bidirectional"))
    )
    (net (code "71") (name "unconnected-(IC1-PE2(~{HWB})-Pad33)") (class "Default")
      (node (ref "IC1") (pin "33") (pinfunction "PE2(~{HWB})_33") (pintype "bidirectional"))
    )
    (net (code "72") (name "unconnected-(IC1-PE6(INT.6{slash}AIN0)-Pad1)") (class "Default")
      (node (ref "IC1") (pin "1") (pinfunction "PE6(INT.6/AIN0)_1") (pintype "bidirectional"))
    )
    (net (code "73") (name "unconnected-(IC1-PF7(ADC7{slash}TDI)-Pad36)") (class "Default")
      (node (ref "IC1") (pin "36") (pinfunction "PF7(ADC7/TDI)_36") (pintype "bidirectional"))
    )
    (net (code "74") (name "unconnected-(IC2-AUDIOIN-Pad17)") (class "Default")
      (node (ref "IC2") (pin "17") (pinfunction "AUDIOIN_17") (pintype "input"))
    )
    (net (code "75") (name "unconnected-(IC2-CB1-Pad7)") (class "Default")
      (node (ref "IC2") (pin "7") (pinfunction "CB1_7") (pintype "bidirectional"))
    )
    (net (code "76") (name "unconnected-(IC2-CB2-Pad8)") (class "Default")
      (node (ref "IC2") (pin "8") (pinfunction "CB2_8") (pintype "bidirectional"))
    )
    (net (code "77") (name "unconnected-(IC2-CB3-Pad9)") (class "Default")
      (node (ref "IC2") (pin "9") (pinfunction "CB3_9") (pintype "bidirectional"))
    )
    (net (code "78") (name "unconnected-(IC2-CB4-Pad10)") (class "Default")
      (node (ref "IC2") (pin "10") (pinfunction "CB4_10") (pintype "bidirectional"))
    )
    (net (code "79") (name "unconnected-(IC2-CB5-Pad11)") (class "Default")
      (node (ref "IC2") (pin "11") (pinfunction "CB5_11") (pintype "bidirectional"))
    )
    (net (code "80") (name "unconnected-(IC2-CB6-Pad12)") (class "Default")
      (node (ref "IC2") (pin "12") (pinfunction "CB6_12") (pintype "bidirectional"))
    )
    (net (code "81") (name "unconnected-(IC2-CB7-Pad13)") (class "Default")
      (node (ref "IC2") (pin "13") (pinfunction "CB7_13") (pintype "bidirectional"))
    )
    (net (code "82") (name "unconnected-(IC2-CB8-Pad14)") (class "Default")
      (node (ref "IC2") (pin "14") (pinfunction "CB8_14") (pintype "bidirectional"))
    )
    (net (code "83") (name "unconnected-(IC2-CB9-Pad15)") (class "Default")
      (node (ref "IC2") (pin "15") (pinfunction "CB9_15") (pintype "bidirectional"))
    )
    (net (code "84") (name "unconnected-(IC2-INTB-Pad4)") (class "Default")
      (node (ref "IC2") (pin "4") (pinfunction "INTB_4") (pintype "output"))
    )
    (net (code "85") (name "unconnected-(SW3-0-Pad1)") (class "Default")
      (node (ref "SW3") (pin "1") (pinfunction "0_1") (pintype "passive"))
    )
    (net (code "86") (name "unconnected-(SW3-1-Pad4)") (class "Default")
      (node (ref "SW3") (pin "4") (pinfunction "1_4") (pintype "passive"))
    )
  )
)
